# AUDIO_CODEC.net
KiCad netlist of a schematic drawn in Altium Designer
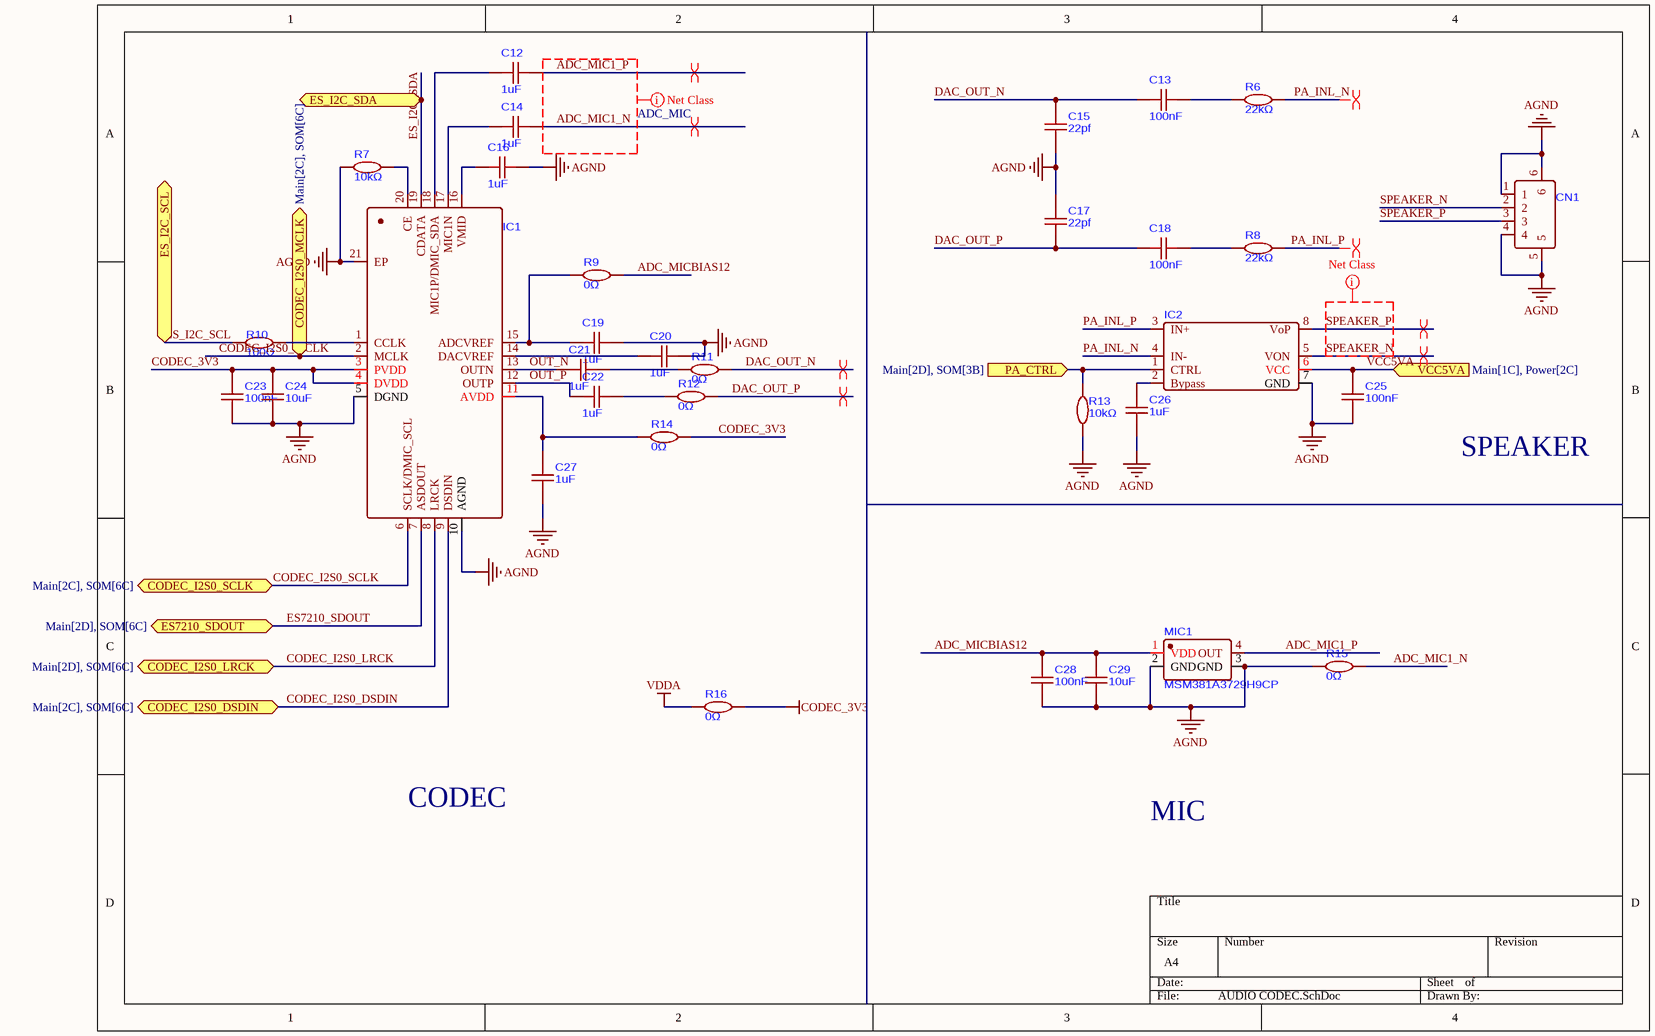
[diagram p0: AUDIO CODEC.SchDoc]

(export (version "E")
  (design (tool "Eeschema 10.0.6"))
  (components
    (comp (ref "C12")
      (value "1uF")
      (footprint "C0603")
      (description "25V 1uF X7R ±10% 0603 Ceramic Capacitors ROHS")
      (libsource (lib "Schlib2") (part "CL10B105KA8NNNC"))
    )
    (comp (ref "C13")
      (value "100nF")
      (footprint "C0603")
      (description "50V 100nF X7R ±10% 0603 Ceramic Capacitors ROHS")
      (libsource (lib "Schlib2") (part "CC0603KRX7R9BB104"))
    )
    (comp (ref "C14")
      (value "1uF")
      (footprint "C0603")
      (description "25V 1uF X7R ±10% 0603 Ceramic Capacitors ROHS")
      (libsource (lib "Schlib2") (part "CL10B105KA8NNNC"))
    )
    (comp (ref "C15")
      (value "22pf")
      (footprint "C0603")
      (description "50V 22pF C0G ±5% 0603 Ceramic Capacitors RoHS")
      (libsource (lib "Schlib2") (part "CL10C220JB8NNNC"))
    )
    (comp (ref "C16")
      (value "1uF")
      (footprint "C0603")
      (description "25V 1uF X7R ±10% 0603 Ceramic Capacitors ROHS")
      (libsource (lib "Schlib2") (part "CL10B105KA8NNNC"))
    )
    (comp (ref "C17")
      (value "22pf")
      (footprint "C0603")
      (description "50V 22pF C0G ±5% 0603 Ceramic Capacitors RoHS")
      (libsource (lib "Schlib2") (part "CL10C220JB8NNNC"))
    )
    (comp (ref "C18")
      (value "100nF")
      (footprint "C0603")
      (description "50V 100nF X7R ±10% 0603 Ceramic Capacitors ROHS")
      (libsource (lib "Schlib2") (part "CC0603KRX7R9BB104"))
    )
    (comp (ref "C19")
      (value "1uF")
      (footprint "C0603")
      (description "25V 1uF X7R ±10% 0603 Ceramic Capacitors ROHS")
      (libsource (lib "Schlib2") (part "CL10B105KA8NNNC"))
    )
    (comp (ref "C20")
      (value "1uF")
      (footprint "C0603")
      (description "25V 1uF X7R ±10% 0603 Ceramic Capacitors ROHS")
      (libsource (lib "Schlib2") (part "CL10B105KA8NNNC"))
    )
    (comp (ref "C21")
      (value "1uF")
      (footprint "C0603")
      (description "25V 1uF X7R ±10% 0603 Ceramic Capacitors ROHS")
      (libsource (lib "Schlib2") (part "CL10B105KA8NNNC"))
    )
    (comp (ref "C22")
      (value "1uF")
      (footprint "C0603")
      (description "25V 1uF X7R ±10% 0603 Ceramic Capacitors ROHS")
      (libsource (lib "Schlib2") (part "CL10B105KA8NNNC"))
    )
    (comp (ref "C23")
      (value "100nF")
      (footprint "C0603")
      (description "50V 100nF X7R ±10% 0603 Ceramic Capacitors ROHS")
      (libsource (lib "Schlib2") (part "CC0603KRX7R9BB104"))
    )
    (comp (ref "C24")
      (value "10uF")
      (footprint "C0603")
      (description "25V 10uF X5R ±20% 0603 Ceramic Capacitors ROHS")
      (libsource (lib "Schlib2") (part "CL10A106MA8NRNC"))
    )
    (comp (ref "C25")
      (value "100nF")
      (footprint "C0603")
      (description "50V 100nF X7R ±10% 0603 Ceramic Capacitors ROHS")
      (libsource (lib "Schlib2") (part "CC0603KRX7R9BB104"))
    )
    (comp (ref "C26")
      (value "1uF")
      (footprint "C0603")
      (description "25V 1uF X7R ±10% 0603 Ceramic Capacitors ROHS")
      (libsource (lib "Schlib2") (part "CL10B105KA8NNNC"))
    )
    (comp (ref "C27")
      (value "1uF")
      (footprint "C0603")
      (description "25V 1uF X7R ±10% 0603 Ceramic Capacitors ROHS")
      (libsource (lib "Schlib2") (part "CL10B105KA8NNNC"))
    )
    (comp (ref "C28")
      (value "100nF")
      (footprint "C0603")
      (description "50V 100nF X7R ±10% 0603 Ceramic Capacitors ROHS")
      (libsource (lib "Schlib2") (part "CC0603KRX7R9BB104"))
    )
    (comp (ref "C29")
      (value "10uF")
      (footprint "C0603")
      (description "25V 10uF X5R ±20% 0603 Ceramic Capacitors ROHS")
      (libsource (lib "Schlib2") (part "CL10A106MA8NRNC"))
    )
    (comp (ref "CN1")
      (value "533980471")
      (footprint "CONN-SMD_4P-P1.25_XUNPU_WAFER-GH1.25-4PWB")
      (libsource (lib "Schlib2") (part "533980471"))
    )
    (comp (ref "IC1")
      (value "Low Power Mono Audio CODEC")
      (footprint "WQFN-20_L3.0-W3.0-P0.40-BL-EP1.7")
      (description "1.8V~3.3V QFN-20-EP(3x3) Signal Switches, Multiplexers, Decoders RoHS")
      (libsource (lib "Schlib2") (part "ES8311"))
    )
    (comp (ref "IC2")
      (value "NS4150B 3.0W Mono Class-D Audio Power Amplifier")
      (footprint "MSOP-8_L3.0-W3.0-P0.65-LS5.0-BL")
      (description "4mA 1-Channel 3Wx1@4Ω Class D MSOP-8 Audio Amplifiers RoHS")
      (libsource (lib "Schlib2") (part "NS4150"))
    )
    (comp (ref "MIC1")
      (value "MSM381A3729H9CP")
      (footprint "MIC-SMD_4P-L3.8-W3.0-P2.46-S1.70-TR")
      (description "OCLGA-4(3x3.8) MEMS Microphones ROHS")
      (libsource (lib "Schlib2") (part "MSM381A3729H9CP"))
    )
    (comp (ref "R6")
      (value "22kΩ")
      (footprint "R0603")
      (description "100mW 22kΩ 75V ±100ppm/℃ Thick Film Resistor ±1% 0603 Chip Resistor - Surface Mount RoHS")
      (libsource (lib "Schlib2") (part "RC0603FR-0722KL"))
    )
    (comp (ref "R7")
      (value "10kΩ")
      (footprint "R0603")
      (description "100mW 10kΩ 75V ±100ppm/℃ Thick Film Resistor ±1% 0603 Chip Resistor - Surface Mount ROHS")
      (libsource (lib "Schlib2") (part "RC0603FR-0710KL"))
    )
    (comp (ref "R8")
      (value "22kΩ")
      (footprint "R0603")
      (description "100mW 22kΩ 75V ±100ppm/℃ Thick Film Resistor ±1% 0603 Chip Resistor - Surface Mount RoHS")
      (libsource (lib "Schlib2") (part "RC0603FR-0722KL"))
    )
    (comp (ref "R9")
      (value "0Ω")
      (footprint "R0603")
      (description "100mW 0Ω 75V Thick Film Resistor ±5% 0603 Chip Resistor - Surface Mount RoHS")
      (libsource (lib "Schlib2") (part "RC0603JR-070RL"))
    )
    (comp (ref "R10")
      (value "100Ω")
      (footprint "R0603")
      (description "100mW 100Ω 75V ±100ppm/℃ Thick Film Resistor ±1% 0603 Chip Resistor - Surface Mount ROHS")
      (libsource (lib "Schlib2") (part "RC0603FR-07100RL"))
    )
    (comp (ref "R11")
      (value "0Ω")
      (footprint "R0603")
      (description "100mW 0Ω 75V Thick Film Resistor ±5% 0603 Chip Resistor - Surface Mount RoHS")
      (libsource (lib "Schlib2") (part "RC0603JR-070RL"))
    )
    (comp (ref "R12")
      (value "0Ω")
      (footprint "R0603")
      (description "100mW 0Ω 75V Thick Film Resistor ±5% 0603 Chip Resistor - Surface Mount RoHS")
      (libsource (lib "Schlib2") (part "RC0603JR-070RL"))
    )
    (comp (ref "R13")
      (value "10kΩ")
      (footprint "R0603")
      (description "100mW 10kΩ 75V ±100ppm/℃ Thick Film Resistor ±1% 0603 Chip Resistor - Surface Mount ROHS")
      (libsource (lib "Schlib2") (part "RC0603FR-0710KL"))
    )
    (comp (ref "R14")
      (value "0Ω")
      (footprint "R0603")
      (description "100mW 0Ω 75V Thick Film Resistor ±5% 0603 Chip Resistor - Surface Mount RoHS")
      (libsource (lib "Schlib2") (part "RC0603JR-070RL"))
    )
    (comp (ref "R15")
      (value "0Ω")
      (footprint "R0603")
      (description "100mW 0Ω 75V Thick Film Resistor ±5% 0603 Chip Resistor - Surface Mount RoHS")
      (libsource (lib "Schlib2") (part "RC0603JR-070RL"))
    )
    (comp (ref "R16")
      (value "0Ω")
      (footprint "R0603")
      (description "100mW 0Ω 75V Thick Film Resistor ±5% 0603 Chip Resistor - Surface Mount RoHS")
      (libsource (lib "Schlib2") (part "RC0603JR-070RL"))
    )
  )
  (nets
    (net (code "1") (name "/ADC_MIC1_N") (class "Default")
      (node (ref "C14") (pin "1") (pinfunction "1_1") (pintype "passive"))
      (node (ref "R15") (pin "2") (pinfunction "2_2") (pintype "passive"))
    )
    (net (code "2") (name "/ADC_MIC1_P") (class "Default")
      (node (ref "C12") (pin "2") (pinfunction "2_2") (pintype "passive"))
      (node (ref "MIC1") (pin "4") (pinfunction "OUT_4") (pintype "passive"))
    )
    (net (code "3") (name "/ADC_MICBIAS12") (class "Default")
      (node (ref "C28") (pin "2") (pinfunction "2_2") (pintype "passive"))
      (node (ref "C29") (pin "2") (pinfunction "2_2") (pintype "passive"))
      (node (ref "MIC1") (pin "1") (pinfunction "VDD_1") (pintype "passive"))
      (node (ref "R9") (pin "2") (pinfunction "2_2") (pintype "passive"))
    )
    (net (code "4") (name "/CODEC_I2S0_DSDIN") (class "Default")
      (node (ref "IC1") (pin "9") (pinfunction "DSDIN_9") (pintype "passive"))
    )
    (net (code "5") (name "/CODEC_I2S0_LRCK") (class "Default")
      (node (ref "IC1") (pin "8") (pinfunction "LRCK_8") (pintype "passive"))
    )
    (net (code "6") (name "/CODEC_I2S0_MCLK") (class "Default")
      (node (ref "IC1") (pin "2") (pinfunction "MCLK_2") (pintype "passive"))
    )
    (net (code "7") (name "/CODEC_I2S0_SCLK") (class "Default")
      (node (ref "IC1") (pin "6") (pinfunction "SCLK/DMIC_SCL_6") (pintype "passive"))
    )
    (net (code "8") (name "/DAC_OUT_N") (class "Default")
      (node (ref "C13") (pin "1") (pinfunction "1_1") (pintype "passive"))
      (node (ref "C15") (pin "2") (pinfunction "2_2") (pintype "passive"))
      (node (ref "R11") (pin "2") (pinfunction "2_2") (pintype "passive"))
    )
    (net (code "9") (name "/DAC_OUT_P") (class "Default")
      (node (ref "C17") (pin "1") (pinfunction "1_1") (pintype "passive"))
      (node (ref "C18") (pin "1") (pinfunction "1_1") (pintype "passive"))
      (node (ref "R12") (pin "2") (pinfunction "2_2") (pintype "passive"))
    )
    (net (code "10") (name "/ES7210_SDOUT") (class "Default")
      (node (ref "IC1") (pin "7") (pinfunction "ASDOUT_7") (pintype "passive"))
    )
    (net (code "11") (name "/ES_I2C_SCL") (class "Default")
      (node (ref "R10") (pin "1") (pinfunction "1_1") (pintype "passive"))
    )
    (net (code "12") (name "/ES_I2C_SDA") (class "Default")
      (node (ref "IC1") (pin "19") (pinfunction "CDATA_19") (pintype "passive"))
    )
    (net (code "13") (name "/OUT_N") (class "Default")
      (node (ref "C21") (pin "2") (pinfunction "2_2") (pintype "passive"))
      (node (ref "IC1") (pin "13") (pinfunction "OUTN_13") (pintype "passive"))
    )
    (net (code "14") (name "/OUT_P") (class "Default")
      (node (ref "C22") (pin "2") (pinfunction "2_2") (pintype "passive"))
      (node (ref "IC1") (pin "12") (pinfunction "OUTP_12") (pintype "passive"))
    )
    (net (code "15") (name "/PA_CTRL") (class "Default")
      (node (ref "IC2") (pin "1") (pinfunction "CTRL_1") (pintype "passive"))
      (node (ref "R13") (pin "2") (pinfunction "2_2") (pintype "passive"))
    )
    (net (code "16") (name "/PA_INL_N") (class "Default")
      (node (ref "IC2") (pin "4") (pinfunction "IN-_4") (pintype "passive"))
      (node (ref "R6") (pin "2") (pinfunction "2_2") (pintype "passive"))
    )
    (net (code "17") (name "/PA_INL_P") (class "Default")
      (node (ref "IC2") (pin "3") (pinfunction "IN+_3") (pintype "passive"))
      (node (ref "R8") (pin "2") (pinfunction "2_2") (pintype "passive"))
    )
    (net (code "18") (name "/SPEAKER_N") (class "Default")
      (node (ref "CN1") (pin "2") (pinfunction "2_2") (pintype "passive"))
      (node (ref "IC2") (pin "5") (pinfunction "VON_5") (pintype "passive"))
    )
    (net (code "19") (name "/SPEAKER_P") (class "Default")
      (node (ref "CN1") (pin "3") (pinfunction "3_3") (pintype "passive"))
      (node (ref "IC2") (pin "8") (pinfunction "VoP_8") (pintype "passive"))
    )
    (net (code "20") (name "/VCC5VA") (class "Default")
      (node (ref "C25") (pin "2") (pinfunction "2_2") (pintype "passive"))
      (node (ref "IC2") (pin "6") (pinfunction "VCC_6") (pintype "passive"))
    )
    (net (code "21") (name "AGND") (class "Default")
      (node (ref "C15") (pin "1") (pinfunction "1_1") (pintype "passive"))
      (node (ref "C16") (pin "1") (pinfunction "1_1") (pintype "passive"))
      (node (ref "C17") (pin "2") (pinfunction "2_2") (pintype "passive"))
      (node (ref "C19") (pin "1") (pinfunction "1_1") (pintype "passive"))
      (node (ref "C20") (pin "1") (pinfunction "1_1") (pintype "passive"))
      (node (ref "C23") (pin "1") (pinfunction "1_1") (pintype "passive"))
      (node (ref "C24") (pin "1") (pinfunction "1_1") (pintype "passive"))
      (node (ref "C25") (pin "1") (pinfunction "1_1") (pintype "passive"))
      (node (ref "C26") (pin "1") (pinfunction "1_1") (pintype "passive"))
      (node (ref "C27") (pin "2") (pinfunction "2_2") (pintype "passive"))
      (node (ref "C28") (pin "1") (pinfunction "1_1") (pintype "passive"))
      (node (ref "C29") (pin "1") (pinfunction "1_1") (pintype "passive"))
      (node (ref "CN1") (pin "1") (pinfunction "1_1") (pintype "passive"))
      (node (ref "CN1") (pin "4") (pinfunction "4_4") (pintype "passive"))
      (node (ref "CN1") (pin "5") (pinfunction "5_5") (pintype "passive"))
      (node (ref "CN1") (pin "6") (pinfunction "6_6") (pintype "passive"))
      (node (ref "IC1") (pin "10") (pinfunction "AGND_10") (pintype "passive"))
      (node (ref "IC1") (pin "21") (pinfunction "EP_21") (pintype "passive"))
      (node (ref "IC1") (pin "5") (pinfunction "DGND_5") (pintype "passive"))
      (node (ref "IC2") (pin "7") (pinfunction "GND_7") (pintype "passive"))
      (node (ref "MIC1") (pin "2") (pinfunction "GND_2") (pintype "passive"))
      (node (ref "MIC1") (pin "3") (pinfunction "GND_3") (pintype "passive"))
      (node (ref "R13") (pin "1") (pinfunction "1_1") (pintype "passive"))
      (node (ref "R15") (pin "1") (pinfunction "1_1") (pintype "passive"))
      (node (ref "R7") (pin "1") (pinfunction "1_1") (pintype "passive"))
    )
    (net (code "22") (name "CODEC_3V3") (class "Default")
      (node (ref "C23") (pin "2") (pinfunction "2_2") (pintype "passive"))
      (node (ref "C24") (pin "2") (pinfunction "2_2") (pintype "passive"))
      (node (ref "IC1") (pin "3") (pinfunction "PVDD_3") (pintype "passive"))
      (node (ref "IC1") (pin "4") (pinfunction "DVDD_4") (pintype "passive"))
      (node (ref "R14") (pin "2") (pinfunction "2_2") (pintype "passive"))
      (node (ref "R16") (pin "2") (pinfunction "2_2") (pintype "passive"))
    )
    (net (code "23") (name "Net-(C13-Pad2)") (class "Default")
      (node (ref "C13") (pin "2") (pinfunction "2_2") (pintype "passive"))
      (node (ref "R6") (pin "1") (pinfunction "1_1") (pintype "passive"))
    )
    (net (code "24") (name "Net-(C18-Pad2)") (class "Default")
      (node (ref "C18") (pin "2") (pinfunction "2_2") (pintype "passive"))
      (node (ref "R8") (pin "1") (pinfunction "1_1") (pintype "passive"))
    )
    (net (code "25") (name "Net-(C21-Pad1)") (class "Default")
      (node (ref "C21") (pin "1") (pinfunction "1_1") (pintype "passive"))
      (node (ref "R11") (pin "1") (pinfunction "1_1") (pintype "passive"))
    )
    (net (code "26") (name "Net-(C22-Pad1)") (class "Default")
      (node (ref "C22") (pin "1") (pinfunction "1_1") (pintype "passive"))
      (node (ref "R12") (pin "1") (pinfunction "1_1") (pintype "passive"))
    )
    (net (code "27") (name "Net-(IC1-ADCVREF)") (class "Default")
      (node (ref "C19") (pin "2") (pinfunction "2_2") (pintype "passive"))
      (node (ref "IC1") (pin "15") (pinfunction "ADCVREF_15") (pintype "passive"))
      (node (ref "R9") (pin "1") (pinfunction "1_1") (pintype "passive"))
    )
    (net (code "28") (name "Net-(IC1-AVDD)") (class "Default")
      (node (ref "C27") (pin "1") (pinfunction "1_1") (pintype "passive"))
      (node (ref "IC1") (pin "11") (pinfunction "AVDD_11") (pintype "passive"))
      (node (ref "R14") (pin "1") (pinfunction "1_1") (pintype "passive"))
    )
    (net (code "29") (name "Net-(IC1-CCLK)") (class "Default")
      (node (ref "IC1") (pin "1") (pinfunction "CCLK_1") (pintype "passive"))
      (node (ref "R10") (pin "2") (pinfunction "2_2") (pintype "passive"))
    )
    (net (code "30") (name "Net-(IC1-CE)") (class "Default")
      (node (ref "IC1") (pin "20") (pinfunction "CE_20") (pintype "passive"))
      (node (ref "R7") (pin "2") (pinfunction "2_2") (pintype "passive"))
    )
    (net (code "31") (name "Net-(IC1-DACVREF)") (class "Default")
      (node (ref "C20") (pin "2") (pinfunction "2_2") (pintype "passive"))
      (node (ref "IC1") (pin "14") (pinfunction "DACVREF_14") (pintype "passive"))
    )
    (net (code "32") (name "Net-(IC1-MIC1N)") (class "Default")
      (node (ref "C14") (pin "2") (pinfunction "2_2") (pintype "passive"))
      (node (ref "IC1") (pin "17") (pinfunction "MIC1N_17") (pintype "passive"))
    )
    (net (code "33") (name "Net-(IC1-MIC1P{slash}DMIC_SDA)") (class "Default")
      (node (ref "C12") (pin "1") (pinfunction "1_1") (pintype "passive"))
      (node (ref "IC1") (pin "18") (pinfunction "MIC1P/DMIC_SDA_18") (pintype "passive"))
    )
    (net (code "34") (name "Net-(IC1-VMID)") (class "Default")
      (node (ref "C16") (pin "2") (pinfunction "2_2") (pintype "passive"))
      (node (ref "IC1") (pin "16") (pinfunction "VMID_16") (pintype "passive"))
    )
    (net (code "35") (name "Net-(IC2-Bypass)") (class "Default")
      (node (ref "C26") (pin "2") (pinfunction "2_2") (pintype "passive"))
      (node (ref "IC2") (pin "2") (pinfunction "Bypass_2") (pintype "passive"))
    )
    (net (code "36") (name "VDDA") (class "Default")
      (node (ref "R16") (pin "1") (pinfunction "1_1") (pintype "passive"))
    )
  )
)
